# 5V_Converter.net
KiCad netlist of a schematic drawn in Altium Designer
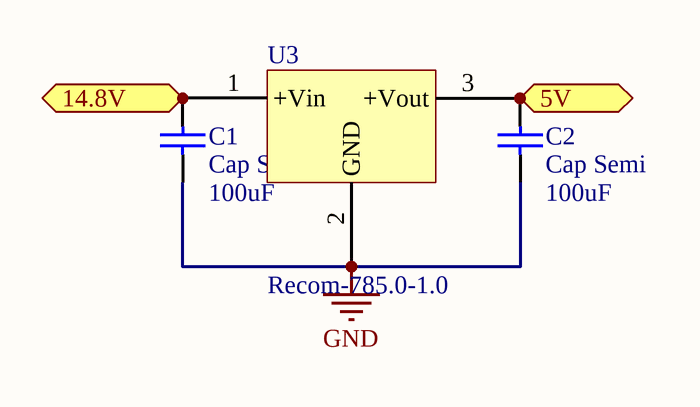
[diagram p0: 5V_Converter.SchDoc]

(export (version "E")
  (design (tool "Eeschema 10.0.6"))
  (components
    (comp (ref "C1")
      (value "Cap Semi")
      (footprint "C1206")
      (description "Capacitor (Semiconductor SIM Model)")
      (fields (field (name "ALTIUM_VALUE") "100uF") (field (name "PUBLISHER") "Altium Limited"))
      (libsource (lib "Miscellaneous Devices") (part "Cap Semi"))
    )
    (comp (ref "C2")
      (value "Cap Semi")
      (footprint "C1206")
      (description "Capacitor (Semiconductor SIM Model)")
      (fields (field (name "ALTIUM_VALUE") "100uF") (field (name "PUBLISHER") "Altium Limited"))
      (libsource (lib "Miscellaneous Devices") (part "Cap Semi"))
    )
    (comp (ref "U3")
      (value "Recom-785.0-1.0")
      (footprint "Recom-78E5.0-1.0")
      (libsource (lib "Recom-78E5.0-1.0") (part "Recom-785.0-1.0"))
    )
  )
  (nets
    (net (code "1") (name "/5V") (class "Default")
      (node (ref "C2") (pin "2") (pinfunction "2_2") (pintype "passive"))
      (node (ref "U3") (pin "3") (pinfunction "+Vout_3") (pintype "passive"))
    )
    (net (code "2") (name "/14.8V") (class "Default")
      (node (ref "C1") (pin "2") (pinfunction "2_2") (pintype "passive"))
      (node (ref "U3") (pin "1") (pinfunction "+Vin_1") (pintype "passive"))
    )
    (net (code "3") (name "GND") (class "Default")
      (node (ref "C1") (pin "1") (pinfunction "1_1") (pintype "passive"))
      (node (ref "C2") (pin "1") (pinfunction "1_1") (pintype "passive"))
      (node (ref "U3") (pin "2") (pinfunction "GND_2") (pintype "passive"))
    )
  )
)
